# Transformerless_Power_Supply.net
KiCad netlist of a schematic drawn in EAGLE
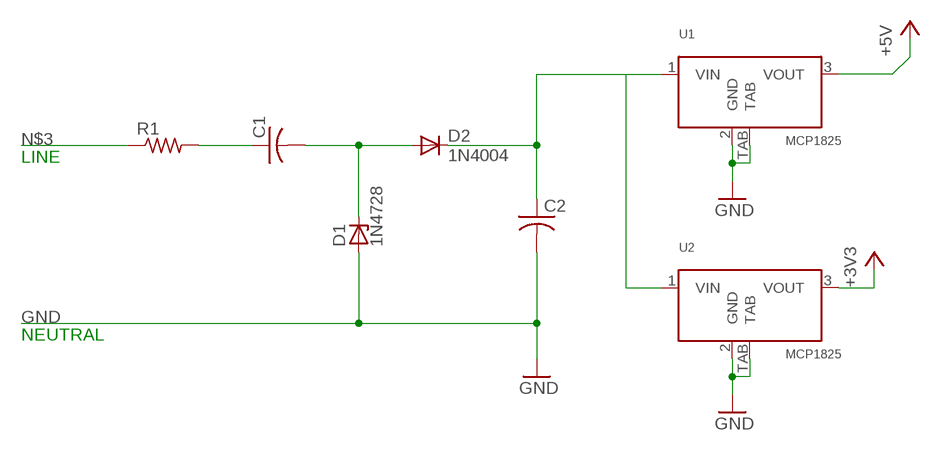
[diagram p0: schematic, sheet 1]

(export (version "E")
  (design (tool "Eeschema 10.0.6"))
  (components
    (comp (ref "C1")
      (value "C-US025-024X044")
      (footprint "eagle-import:C025-024X044")
      (libsource (lib "eagle-import") (part "C-US025-024X044"))
    )
    (comp (ref "C2")
      (value "C-US025-024X044")
      (footprint "eagle-import:C025-024X044")
      (libsource (lib "eagle-import") (part "C-US025-024X044"))
    )
    (comp (ref "D1")
      (value "1N4728")
      (footprint "eagle-import:DO41Z10")
      (libsource (lib "eagle-import") (part "1N4728"))
    )
    (comp (ref "D2")
      (value "1N4004")
      (footprint "eagle-import:DO41-10")
      (libsource (lib "eagle-import") (part "1N4004"))
    )
    (comp (ref "R1")
      (value "R-US_0204/2V")
      (footprint "eagle-import:0204V")
      (libsource (lib "eagle-import") (part "R-US_0204/2V"))
    )
    (comp (ref "U1")
      (value "MCP1825")
      (footprint "eagle-import:SOT223_MICROCHIP")
      (libsource (lib "eagle-import") (part "MCP1825"))
    )
    (comp (ref "U2")
      (value "MCP1825")
      (footprint "eagle-import:SOT223_MICROCHIP")
      (libsource (lib "eagle-import") (part "MCP1825"))
    )
  )
  (nets
    (net (code "1") (name "+3V3") (class "Default")
      (node (ref "U2") (pin "3") (pinfunction "VOUT_3") (pintype "bidirectional"))
    )
    (net (code "2") (name "+5V") (class "Default")
      (node (ref "U1") (pin "3") (pinfunction "VOUT_3") (pintype "bidirectional"))
    )
    (net (code "3") (name "/LINE") (class "Default")
      (node (ref "C2") (pin "1") (pinfunction "1_1") (pintype "passive"))
      (node (ref "D2") (pin "C") (pinfunction "C_C") (pintype "passive"))
      (node (ref "R1") (pin "1") (pinfunction "1_1") (pintype "passive"))
      (node (ref "U1") (pin "1") (pinfunction "VIN_1") (pintype "bidirectional"))
      (node (ref "U2") (pin "1") (pinfunction "VIN_1") (pintype "bidirectional"))
    )
    (net (code "4") (name "/N$3") (class "Default")
      (node (ref "C1") (pin "2") (pinfunction "2_2") (pintype "passive"))
      (node (ref "D1") (pin "C") (pinfunction "C_C") (pintype "passive"))
      (node (ref "D2") (pin "A") (pinfunction "A_A") (pintype "passive"))
    )
    (net (code "5") (name "GND") (class "Default")
      (node (ref "C2") (pin "2") (pinfunction "2_2") (pintype "passive"))
      (node (ref "D1") (pin "A") (pinfunction "A_A") (pintype "passive"))
      (node (ref "U1") (pin "2") (pinfunction "GND_2") (pintype "bidirectional"))
      (node (ref "U1") (pin "TAB") (pinfunction "TAB_TAB") (pintype "bidirectional"))
      (node (ref "U2") (pin "2") (pinfunction "GND_2") (pintype "bidirectional"))
      (node (ref "U2") (pin "TAB") (pinfunction "TAB_TAB") (pintype "bidirectional"))
    )
    (net (code "6") (name "Net-(C1-Pad1)") (class "Default")
      (node (ref "C1") (pin "1") (pinfunction "1_1") (pintype "passive"))
      (node (ref "R1") (pin "2") (pinfunction "2_2") (pintype "passive"))
    )
  )
)
